# Top_Level.net
KiCad netlist of a schematic drawn in Altium Designer
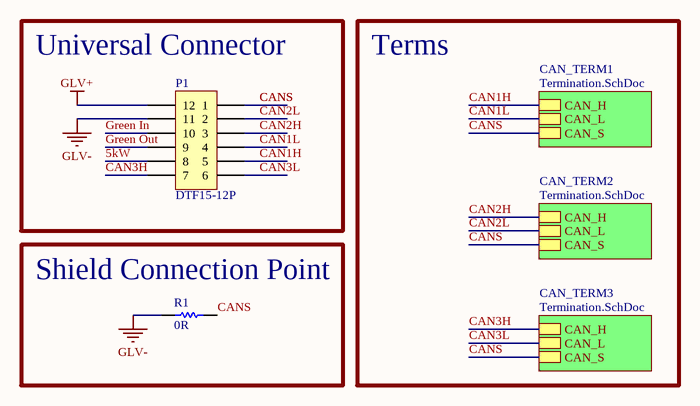
[diagram p0: Top_Level.SchDoc]

(export (version "E")
  (design (tool "Eeschema 10.0.6"))
  (components
    (comp (ref "P1")
      (value "DTF15-12P")
      (footprint "DTF15-12P")
      (fields (field (name "DIGIKEY PART NUMBER") "1734-1647-ND") (field (name "CONTACT") "Copper Alloy"))
      (libsource (lib "ts_20-standard-connectors") (part "DT15-12P"))
    )
    (comp (ref "R1")
      (value "0R")
      (footprint "0805")
      (description "DNP")
      (fields (field (name "PART NUMBER") "RC0805FR070RL") (field (name "MANUFACTURER") "YAGEO"))
      (libsource (lib "ts_20-standard-library") (part "Resistor"))
    )
  )
  (nets
    (net (code "1") (name "/5kW") (class "Default")
      (node (ref "P1") (pin "8") (pinfunction "8_8") (pintype "passive"))
    )
    (net (code "2") (name "/CAN1H") (class "Default")
      (node (ref "P1") (pin "5") (pinfunction "5_5") (pintype "power_in"))
    )
    (net (code "3") (name "/CAN1L") (class "Default")
      (node (ref "P1") (pin "4") (pinfunction "4_4") (pintype "power_in"))
    )
    (net (code "4") (name "/CAN2H") (class "Default")
      (node (ref "P1") (pin "3") (pinfunction "3_3") (pintype "power_in"))
    )
    (net (code "5") (name "/CAN2L") (class "Default")
      (node (ref "P1") (pin "2") (pinfunction "2_2") (pintype "power_in"))
    )
    (net (code "6") (name "/CAN3H") (class "Default")
      (node (ref "P1") (pin "7") (pinfunction "7_7") (pintype "passive"))
    )
    (net (code "7") (name "/CAN3L") (class "Default")
      (node (ref "P1") (pin "6") (pinfunction "6_6") (pintype "power_in"))
    )
    (net (code "8") (name "/CANS") (class "Default")
      (node (ref "P1") (pin "1") (pinfunction "1_1") (pintype "power_in"))
      (node (ref "R1") (pin "2") (pinfunction "2_2") (pintype "passive"))
    )
    (net (code "9") (name "/Green In") (class "Default")
      (node (ref "P1") (pin "10") (pinfunction "10_10") (pintype "passive"))
    )
    (net (code "10") (name "/Green Out") (class "Default")
      (node (ref "P1") (pin "9") (pinfunction "9_9") (pintype "passive"))
    )
    (net (code "11") (name "GLV+") (class "Default")
      (node (ref "P1") (pin "12") (pinfunction "12_12") (pintype "passive"))
    )
    (net (code "12") (name "GLV-") (class "Default")
      (node (ref "P1") (pin "11") (pinfunction "11_11") (pintype "passive"))
      (node (ref "R1") (pin "1") (pinfunction "1_1") (pintype "passive"))
    )
  )
)
